# LT6656_BREAKOUT.net
KiCad netlist of a schematic drawn in EAGLE
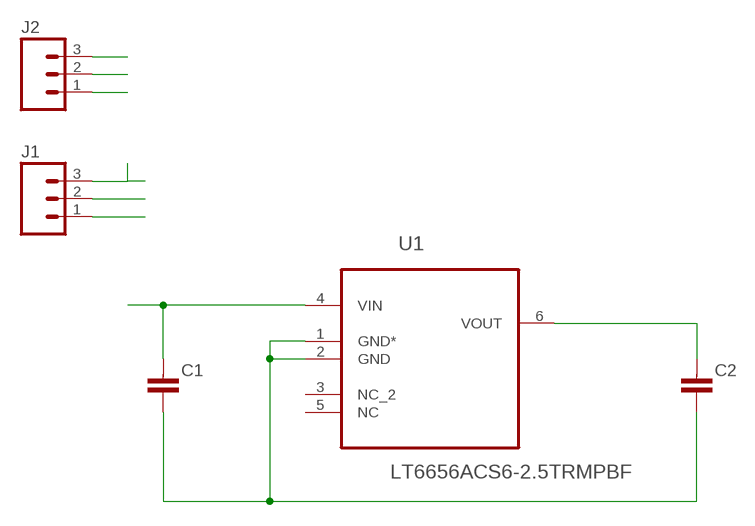
[diagram p0: schematic, sheet 1]

(export (version "E")
  (design (tool "Eeschema 10.0.6"))
  (components
    (comp (ref "C1")
      (value "CAPACITOR0603-N")
      (footprint "eagle-import:C0603-N")
      (libsource (lib "eagle-import") (part "CAPACITOR0603-N"))
    )
    (comp (ref "C2")
      (value "CAPACITOR0603-N")
      (footprint "eagle-import:C0603-N")
      (libsource (lib "eagle-import") (part "CAPACITOR0603-N"))
    )
    (comp (ref "J1")
      (value "M03PTH")
      (footprint "eagle-import:1X03")
      (libsource (lib "eagle-import") (part "M03PTH"))
    )
    (comp (ref "J2")
      (value "M03PTH")
      (footprint "eagle-import:1X03")
      (libsource (lib "eagle-import") (part "M03PTH"))
    )
    (comp (ref "U1")
      (value "LT6656ACS6-2.5TRMPBF")
      (footprint "eagle-import:SOT95P280X100-6N")
      (fields (field (name "MPN") "LT6656ACS6-2.5#TRMPBF"))
      (libsource (lib "eagle-import") (part "LT6656ACS6-2.5TRMPBF"))
    )
  )
  (nets
    (net (code "1") (name "/GND") (class "Default")
      (node (ref "C1") (pin "2") (pinfunction "2_2") (pintype "passive"))
      (node (ref "C2") (pin "2") (pinfunction "2_2") (pintype "passive"))
      (node (ref "J1") (pin "1") (pinfunction "1_1") (pintype "passive"))
      (node (ref "J2") (pin "1") (pinfunction "1_1") (pintype "passive"))
      (node (ref "U1") (pin "1") (pinfunction "GND*_1") (pintype "passive"))
      (node (ref "U1") (pin "2") (pinfunction "GND_2") (pintype "passive"))
    )
    (net (code "2") (name "/OUT") (class "Default")
      (node (ref "J1") (pin "2") (pinfunction "2_2") (pintype "passive"))
      (node (ref "J2") (pin "2") (pinfunction "2_2") (pintype "passive"))
    )
    (net (code "3") (name "/VIN") (class "Default")
      (node (ref "C1") (pin "1") (pinfunction "1_1") (pintype "passive"))
      (node (ref "J1") (pin "3") (pinfunction "3_3") (pintype "passive"))
      (node (ref "U1") (pin "4") (pinfunction "VIN_4") (pintype "input"))
    )
    (net (code "4") (name "/VOUT") (class "Default")
      (node (ref "C2") (pin "1") (pinfunction "1_1") (pintype "passive"))
      (node (ref "J2") (pin "3") (pinfunction "3_3") (pintype "passive"))
      (node (ref "U1") (pin "6") (pinfunction "VOUT_6") (pintype "output"))
    )
    (net (code "5") (name "unconnected-(U1-NC-Pad5)") (class "Default")
      (node (ref "U1") (pin "5") (pinfunction "NC_5") (pintype "no_connect"))
    )
    (net (code "6") (name "unconnected-(U1-NC_2-Pad3)") (class "Default")
      (node (ref "U1") (pin "3") (pinfunction "NC_2_3") (pintype "no_connect"))
    )
  )
)
